# PCB2.net
KiCad netlist of a schematic drawn in EAGLE
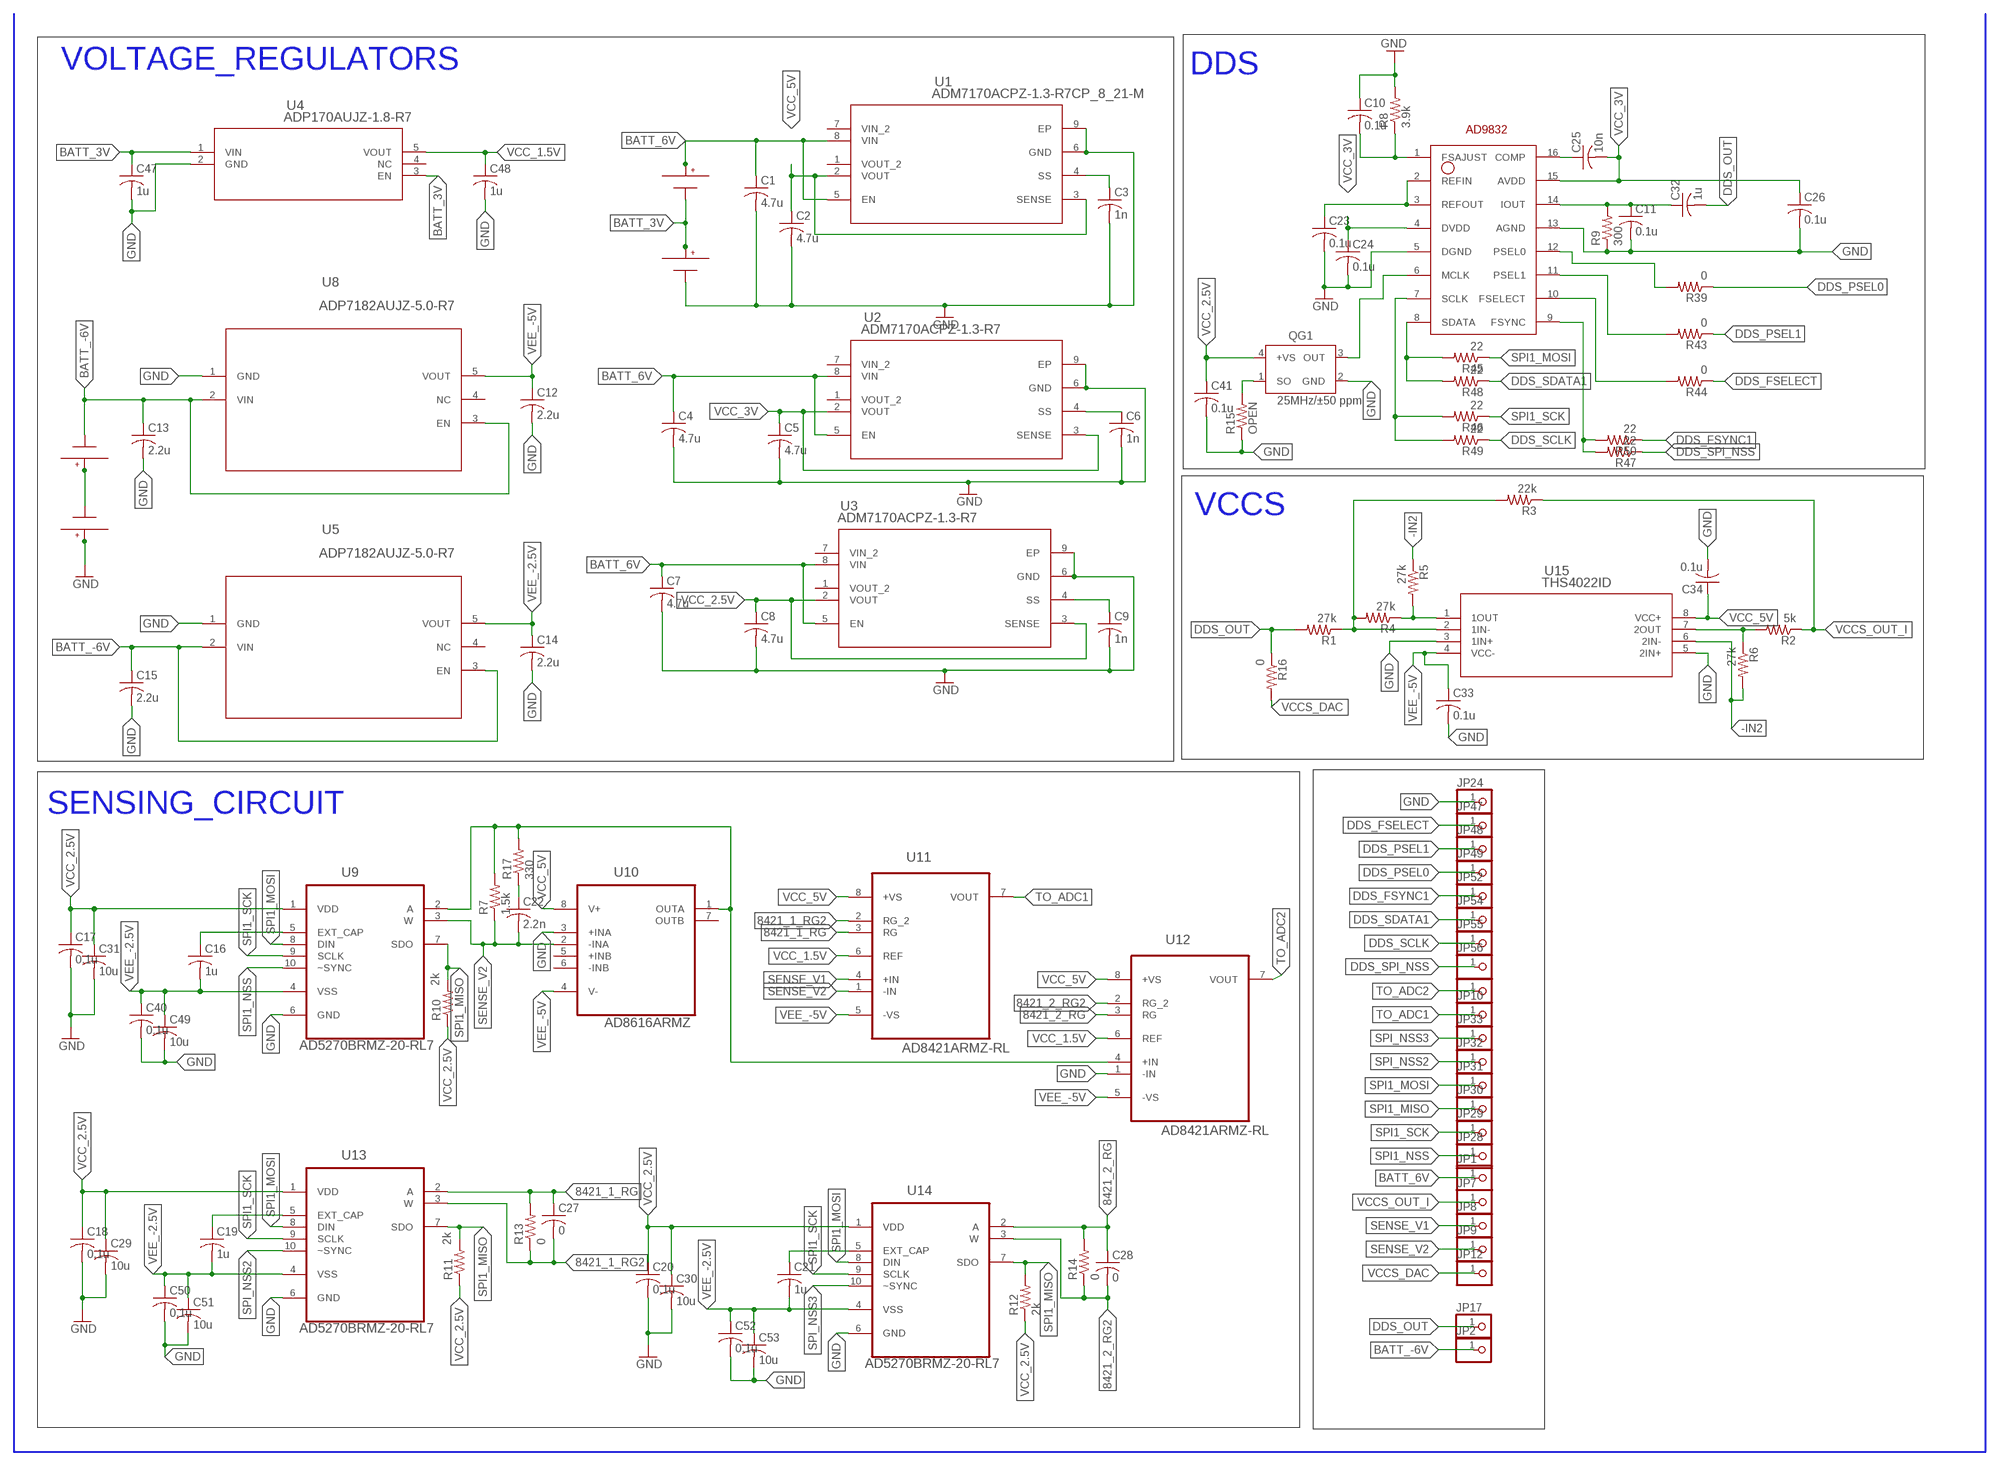
[diagram p0: schematic, sheet 1]

(export (version "E")
  (design (tool "Eeschema 10.0.6"))
  (components
    (comp (ref "C1")
      (value "4.7u")
      (footprint "eagle-import:C0603")
      (libsource (lib "eagle-import") (part "C-USC0603"))
    )
    (comp (ref "C2")
      (value "4.7u")
      (footprint "eagle-import:C0603")
      (libsource (lib "eagle-import") (part "C-USC0603"))
    )
    (comp (ref "C3")
      (value "1n")
      (footprint "eagle-import:C0603")
      (libsource (lib "eagle-import") (part "C-USC0603"))
    )
    (comp (ref "C4")
      (value "4.7u")
      (footprint "eagle-import:C0603")
      (libsource (lib "eagle-import") (part "C-USC0603"))
    )
    (comp (ref "C5")
      (value "4.7u")
      (footprint "eagle-import:C0603")
      (libsource (lib "eagle-import") (part "C-USC0603"))
    )
    (comp (ref "C6")
      (value "1n")
      (footprint "eagle-import:C0603")
      (libsource (lib "eagle-import") (part "C-USC0603"))
    )
    (comp (ref "C7")
      (value "4.7u")
      (footprint "eagle-import:C0603")
      (libsource (lib "eagle-import") (part "C-USC0603"))
    )
    (comp (ref "C8")
      (value "4.7u")
      (footprint "eagle-import:C0603")
      (libsource (lib "eagle-import") (part "C-USC0603"))
    )
    (comp (ref "C9")
      (value "1n")
      (footprint "eagle-import:C0603")
      (libsource (lib "eagle-import") (part "C-USC0603"))
    )
    (comp (ref "C10")
      (value "0.1u")
      (footprint "eagle-import:C0603")
      (libsource (lib "eagle-import") (part "C-USC0603"))
    )
    (comp (ref "C11")
      (value "0.1u")
      (footprint "eagle-import:C0603")
      (libsource (lib "eagle-import") (part "C-USC0603"))
    )
    (comp (ref "C12")
      (value "2.2u")
      (footprint "eagle-import:C0603")
      (libsource (lib "eagle-import") (part "C-USC0603"))
    )
    (comp (ref "C13")
      (value "2.2u")
      (footprint "eagle-import:C0603")
      (libsource (lib "eagle-import") (part "C-USC0603"))
    )
    (comp (ref "C14")
      (value "2.2u")
      (footprint "eagle-import:C0603")
      (libsource (lib "eagle-import") (part "C-USC0603"))
    )
    (comp (ref "C15")
      (value "2.2u")
      (footprint "eagle-import:C0603")
      (libsource (lib "eagle-import") (part "C-USC0603"))
    )
    (comp (ref "C16")
      (value "1u")
      (footprint "eagle-import:C0603")
      (libsource (lib "eagle-import") (part "C-USC0603"))
    )
    (comp (ref "C17")
      (value "0.1u")
      (footprint "eagle-import:C0603")
      (libsource (lib "eagle-import") (part "C-USC0603"))
    )
    (comp (ref "C18")
      (value "0.1u")
      (footprint "eagle-import:C0603")
      (libsource (lib "eagle-import") (part "C-USC0603"))
    )
    (comp (ref "C19")
      (value "1u")
      (footprint "eagle-import:C0603")
      (libsource (lib "eagle-import") (part "C-USC0603"))
    )
    (comp (ref "C20")
      (value "0.1u")
      (footprint "eagle-import:C0603")
      (libsource (lib "eagle-import") (part "C-USC0603"))
    )
    (comp (ref "C21")
      (value "1u")
      (footprint "eagle-import:C0603")
      (libsource (lib "eagle-import") (part "C-USC0603"))
    )
    (comp (ref "C22")
      (value "2.2n")
      (footprint "eagle-import:C0603")
      (libsource (lib "eagle-import") (part "C-USC0603"))
    )
    (comp (ref "C23")
      (value "0.1u")
      (footprint "eagle-import:C0603")
      (libsource (lib "eagle-import") (part "C-USC0603"))
    )
    (comp (ref "C24")
      (value "0.1u")
      (footprint "eagle-import:C0603")
      (libsource (lib "eagle-import") (part "C-USC0603"))
    )
    (comp (ref "C25")
      (value "10n")
      (footprint "eagle-import:C0603")
      (libsource (lib "eagle-import") (part "C-USC0603"))
    )
    (comp (ref "C26")
      (value "0.1u")
      (footprint "eagle-import:C0603")
      (libsource (lib "eagle-import") (part "C-USC0603"))
    )
    (comp (ref "C27")
      (value "0")
      (footprint "eagle-import:C0603")
      (libsource (lib "eagle-import") (part "C-USC0603"))
    )
    (comp (ref "C28")
      (value "0")
      (footprint "eagle-import:C0603")
      (libsource (lib "eagle-import") (part "C-USC0603"))
    )
    (comp (ref "C29")
      (value "10u")
      (footprint "eagle-import:C0603")
      (libsource (lib "eagle-import") (part "C-USC0603"))
    )
    (comp (ref "C30")
      (value "10u")
      (footprint "eagle-import:C0603")
      (libsource (lib "eagle-import") (part "C-USC0603"))
    )
    (comp (ref "C31")
      (value "10u")
      (footprint "eagle-import:C0603")
      (libsource (lib "eagle-import") (part "C-USC0603"))
    )
    (comp (ref "C32")
      (value "1u")
      (footprint "eagle-import:C0603")
      (libsource (lib "eagle-import") (part "C-USC0603"))
    )
    (comp (ref "C33")
      (value "0.1u")
      (footprint "eagle-import:C0603")
      (libsource (lib "eagle-import") (part "C-USC0603"))
    )
    (comp (ref "C34")
      (value "0.1u")
      (footprint "eagle-import:C0603")
      (libsource (lib "eagle-import") (part "C-USC0603"))
    )
    (comp (ref "C40")
      (value "0.1u")
      (footprint "eagle-import:C0603")
      (libsource (lib "eagle-import") (part "C-USC0603"))
    )
    (comp (ref "C41")
      (value "0.1u")
      (footprint "eagle-import:C0603")
      (libsource (lib "eagle-import") (part "C-USC0603"))
    )
    (comp (ref "C47")
      (value "1u")
      (footprint "eagle-import:C0603")
      (libsource (lib "eagle-import") (part "C-USC0603"))
    )
    (comp (ref "C48")
      (value "1u")
      (footprint "eagle-import:C0603")
      (libsource (lib "eagle-import") (part "C-USC0603"))
    )
    (comp (ref "C49")
      (value "10u")
      (footprint "eagle-import:C0603")
      (libsource (lib "eagle-import") (part "C-USC0603"))
    )
    (comp (ref "C50")
      (value "0.1u")
      (footprint "eagle-import:C0603")
      (libsource (lib "eagle-import") (part "C-USC0603"))
    )
    (comp (ref "C51")
      (value "10u")
      (footprint "eagle-import:C0603")
      (libsource (lib "eagle-import") (part "C-USC0603"))
    )
    (comp (ref "C52")
      (value "0.1u")
      (footprint "eagle-import:C0603")
      (libsource (lib "eagle-import") (part "C-USC0603"))
    )
    (comp (ref "C53")
      (value "10u")
      (footprint "eagle-import:C0603")
      (libsource (lib "eagle-import") (part "C-USC0603"))
    )
    (comp (ref "JP1")
      (value "PINHD-1X1")
      (footprint "eagle-import:1X01")
      (libsource (lib "eagle-import") (part "PINHD-1X1"))
    )
    (comp (ref "JP2")
      (value "PINHD-1X1")
      (footprint "eagle-import:1X01")
      (fields (field (name "SPICEPREFIX") "X"))
      (libsource (lib "eagle-import") (part "PINHD-1X1"))
    )
    (comp (ref "JP7")
      (value "PINHD-1X1")
      (footprint "eagle-import:1X01")
      (libsource (lib "eagle-import") (part "PINHD-1X1"))
    )
    (comp (ref "JP8")
      (value "PINHD-1X1")
      (footprint "eagle-import:1X01")
      (libsource (lib "eagle-import") (part "PINHD-1X1"))
    )
    (comp (ref "JP9")
      (value "PINHD-1X1")
      (footprint "eagle-import:1X01")
      (libsource (lib "eagle-import") (part "PINHD-1X1"))
    )
    (comp (ref "JP10")
      (value "PINHD-1X1")
      (footprint "eagle-import:1X01")
      (libsource (lib "eagle-import") (part "PINHD-1X1"))
    )
    (comp (ref "JP11")
      (value "PINHD-1X1")
      (footprint "eagle-import:1X01")
      (libsource (lib "eagle-import") (part "PINHD-1X1"))
    )
    (comp (ref "JP12")
      (value "PINHD-1X1")
      (footprint "eagle-import:1X01")
      (libsource (lib "eagle-import") (part "PINHD-1X1"))
    )
    (comp (ref "JP17")
      (value "PINHD-1X1")
      (footprint "eagle-import:1X01")
      (fields (field (name "SPICEPREFIX") "X"))
      (libsource (lib "eagle-import") (part "PINHD-1X1"))
    )
    (comp (ref "JP24")
      (value "PINHD-1X1")
      (footprint "eagle-import:1X01")
      (libsource (lib "eagle-import") (part "PINHD-1X1"))
    )
    (comp (ref "JP28")
      (value "PINHD-1X1")
      (footprint "eagle-import:1X01")
      (libsource (lib "eagle-import") (part "PINHD-1X1"))
    )
    (comp (ref "JP29")
      (value "PINHD-1X1")
      (footprint "eagle-import:1X01")
      (libsource (lib "eagle-import") (part "PINHD-1X1"))
    )
    (comp (ref "JP30")
      (value "PINHD-1X1")
      (footprint "eagle-import:1X01")
      (libsource (lib "eagle-import") (part "PINHD-1X1"))
    )
    (comp (ref "JP31")
      (value "PINHD-1X1")
      (footprint "eagle-import:1X01")
      (libsource (lib "eagle-import") (part "PINHD-1X1"))
    )
    (comp (ref "JP32")
      (value "PINHD-1X1")
      (footprint "eagle-import:1X01")
      (libsource (lib "eagle-import") (part "PINHD-1X1"))
    )
    (comp (ref "JP33")
      (value "PINHD-1X1")
      (footprint "eagle-import:1X01")
      (libsource (lib "eagle-import") (part "PINHD-1X1"))
    )
    (comp (ref "JP47")
      (value "PINHD-1X1")
      (footprint "eagle-import:1X01")
      (libsource (lib "eagle-import") (part "PINHD-1X1"))
    )
    (comp (ref "JP48")
      (value "PINHD-1X1")
      (footprint "eagle-import:1X01")
      (libsource (lib "eagle-import") (part "PINHD-1X1"))
    )
    (comp (ref "JP49")
      (value "PINHD-1X1")
      (footprint "eagle-import:1X01")
      (libsource (lib "eagle-import") (part "PINHD-1X1"))
    )
    (comp (ref "JP52")
      (value "PINHD-1X1")
      (footprint "eagle-import:1X01")
      (libsource (lib "eagle-import") (part "PINHD-1X1"))
    )
    (comp (ref "JP54")
      (value "PINHD-1X1")
      (footprint "eagle-import:1X01")
      (libsource (lib "eagle-import") (part "PINHD-1X1"))
    )
    (comp (ref "JP55")
      (value "PINHD-1X1")
      (footprint "eagle-import:1X01")
      (libsource (lib "eagle-import") (part "PINHD-1X1"))
    )
    (comp (ref "JP56")
      (value "PINHD-1X1")
      (footprint "eagle-import:1X01")
      (libsource (lib "eagle-import") (part "PINHD-1X1"))
    )
    (comp (ref "QG1")
      (value "25MHz/±50 ppm")
      (footprint "eagle-import:WE-SPXO_IQXO-542")
      (libsource (lib "eagle-import") (part "WE-SPXO_IQXO-542_831056218"))
    )
    (comp (ref "R1")
      (value "27k")
      (footprint "eagle-import:R0603")
      (libsource (lib "eagle-import") (part "R-US_R0603"))
    )
    (comp (ref "R2")
      (value "5k")
      (footprint "eagle-import:R0603")
      (libsource (lib "eagle-import") (part "R-US_R0603"))
    )
    (comp (ref "R3")
      (value "22k")
      (footprint "eagle-import:R0603")
      (libsource (lib "eagle-import") (part "R-US_R0603"))
    )
    (comp (ref "R4")
      (value "27k")
      (footprint "eagle-import:R0603")
      (libsource (lib "eagle-import") (part "R-US_R0603"))
    )
    (comp (ref "R5")
      (value "27k")
      (footprint "eagle-import:R0603")
      (libsource (lib "eagle-import") (part "R-US_R0603"))
    )
    (comp (ref "R6")
      (value "27k")
      (footprint "eagle-import:R0603")
      (libsource (lib "eagle-import") (part "R-US_R0603"))
    )
    (comp (ref "R7")
      (value "1.5k")
      (footprint "eagle-import:R0603")
      (libsource (lib "eagle-import") (part "R-US_R0603"))
    )
    (comp (ref "R8")
      (value "3.9k")
      (footprint "eagle-import:R0603")
      (libsource (lib "eagle-import") (part "R-US_R0603"))
    )
    (comp (ref "R9")
      (value "300")
      (footprint "eagle-import:R0603")
      (libsource (lib "eagle-import") (part "R-US_R0603"))
    )
    (comp (ref "R10")
      (value "2k")
      (footprint "eagle-import:R0603")
      (libsource (lib "eagle-import") (part "R-US_R0603"))
    )
    (comp (ref "R11")
      (value "2k")
      (footprint "eagle-import:R0603")
      (libsource (lib "eagle-import") (part "R-US_R0603"))
    )
    (comp (ref "R12")
      (value "2k")
      (footprint "eagle-import:R0603")
      (libsource (lib "eagle-import") (part "R-US_R0603"))
    )
    (comp (ref "R13")
      (value "0")
      (footprint "eagle-import:R0603")
      (libsource (lib "eagle-import") (part "R-US_R0603"))
    )
    (comp (ref "R14")
      (value "0")
      (footprint "eagle-import:R0603")
      (libsource (lib "eagle-import") (part "R-US_R0603"))
    )
    (comp (ref "R15")
      (value "OPEN")
      (footprint "eagle-import:R0603")
      (libsource (lib "eagle-import") (part "R-US_R0603"))
    )
    (comp (ref "R16")
      (value "0")
      (footprint "eagle-import:R0603")
      (libsource (lib "eagle-import") (part "R-US_R0603"))
    )
    (comp (ref "R17")
      (value "330")
      (footprint "eagle-import:R0603")
      (libsource (lib "eagle-import") (part "R-US_R0603"))
    )
    (comp (ref "R39")
      (value "0")
      (footprint "eagle-import:R0603")
      (libsource (lib "eagle-import") (part "R-US_R0603"))
    )
    (comp (ref "R43")
      (value "0")
      (footprint "eagle-import:R0603")
      (libsource (lib "eagle-import") (part "R-US_R0603"))
    )
    (comp (ref "R44")
      (value "0")
      (footprint "eagle-import:R0603")
      (libsource (lib "eagle-import") (part "R-US_R0603"))
    )
    (comp (ref "R45")
      (value "22")
      (footprint "eagle-import:R0603")
      (libsource (lib "eagle-import") (part "R-US_R0603"))
    )
    (comp (ref "R46")
      (value "22")
      (footprint "eagle-import:R0603")
      (libsource (lib "eagle-import") (part "R-US_R0603"))
    )
    (comp (ref "R47")
      (value "22")
      (footprint "eagle-import:R0603")
      (libsource (lib "eagle-import") (part "R-US_R0603"))
    )
    (comp (ref "R48")
      (value "22")
      (footprint "eagle-import:R0603")
      (libsource (lib "eagle-import") (part "R-US_R0603"))
    )
    (comp (ref "R49")
      (value "22")
      (footprint "eagle-import:R0603")
      (libsource (lib "eagle-import") (part "R-US_R0603"))
    )
    (comp (ref "R50")
      (value "22")
      (footprint "eagle-import:R0603")
      (libsource (lib "eagle-import") (part "R-US_R0603"))
    )
    (comp (ref "U$1")
      (value "AD9832")
      (footprint "eagle-import:TSSOP16")
      (fields (field (name "MF") "Analog Devices"))
      (libsource (lib "eagle-import") (part "AD9832"))
    )
    (comp (ref "U$2")
      (value "BAT-HLD-001")
      (footprint "eagle-import:BAT-HLD-001")
      (fields (field (name "MF") "Linx Technologies"))
      (libsource (lib "eagle-import") (part "BAT-HLD-001"))
    )
    (comp (ref "U$3")
      (value "BAT-HLD-001")
      (footprint "eagle-import:BAT-HLD-001")
      (fields (field (name "MF") "Linx Technologies"))
      (libsource (lib "eagle-import") (part "BAT-HLD-001"))
    )
    (comp (ref "U$4")
      (value "BAT-HLD-001")
      (footprint "eagle-import:BAT-HLD-001")
      (fields (field (name "MF") "Linx Technologies"))
      (libsource (lib "eagle-import") (part "BAT-HLD-001"))
    )
    (comp (ref "U$5")
      (value "BAT-HLD-001")
      (footprint "eagle-import:BAT-HLD-001")
      (fields (field (name "MF") "Linx Technologies"))
      (libsource (lib "eagle-import") (part "BAT-HLD-001"))
    )
    (comp (ref "U1")
      (value "ADM7170ACPZ-1.3-R7CP_8_21-M")
      (footprint "eagle-import:CP_8_21-M")
      (fields (field (name "MANUFACTURER_PART_NUMBER") "ADM7170ACPZ1.3R7"))
      (libsource (lib "eagle-import") (part "ADM7170ACPZ-1.3-R7CP_8_21-M"))
    )
    (comp (ref "U2")
      (value "ADM7170ACPZ-1.3-R7")
      (footprint "eagle-import:CP_8_21")
      (fields (field (name "MANUFACTURER_PART_NUMBER") "ADM7170ACPZ1.3R7"))
      (libsource (lib "eagle-import") (part "ADM7170ACPZ-1.3-R7"))
    )
    (comp (ref "U3")
      (value "ADM7170ACPZ-1.3-R7")
      (footprint "eagle-import:CP_8_21")
      (fields (field (name "MANUFACTURER_PART_NUMBER") "ADM7170ACPZ1.3R7"))
      (libsource (lib "eagle-import") (part "ADM7170ACPZ-1.3-R7"))
    )
    (comp (ref "U4")
      (value "ADP170AUJZ-1.8-R7")
      (footprint "eagle-import:UJ_5")
      (fields (field (name "MANUFACTURER_PART_NUMBER") "ADP170AUJZ1.8R7"))
      (libsource (lib "eagle-import") (part "ADP170AUJZ-1.8-R7"))
    )
    (comp (ref "U5")
      (value "ADP7182AUJZ-5.0-R7")
      (footprint "eagle-import:UJ_5")
      (fields (field (name "MANUFACTURER_PART_NUMBER") "ADP7182AUJZ5.0R7"))
      (libsource (lib "eagle-import") (part "ADP7182AUJZ-5.0-R7"))
    )
    (comp (ref "U8")
      (value "ADP7182AUJZ-5.0-R7")
      (footprint "eagle-import:UJ_5")
      (fields (field (name "MANUFACTURER_PART_NUMBER") "ADP7182AUJZ5.0R7"))
      (libsource (lib "eagle-import") (part "ADP7182AUJZ-5.0-R7"))
    )
    (comp (ref "U9")
      (value "AD5270BRMZ-20-RL7")
      (footprint "eagle-import:SOP50P490X110-10N")
      (fields (field (name "MF") "Analog Devices"))
      (libsource (lib "eagle-import") (part "AD5270BRMZ-20-RL7"))
    )
    (comp (ref "U10")
      (value "AD8616ARMZ")
      (footprint "eagle-import:SOP65P490X110-8N")
      (fields (field (name "MF") "Analog Devices") (field (name "MP") "AD8616ARMZ-REEL"))
      (libsource (lib "eagle-import") (part "AD8616ARMZ"))
    )
    (comp (ref "U11")
      (value "AD8421ARMZ-RL")
      (footprint "eagle-import:SOP65P490X110-8N")
      (fields (field (name "MF") "Analog Devices"))
      (libsource (lib "eagle-import") (part "AD8421ARMZ-RL"))
    )
    (comp (ref "U12")
      (value "AD8421ARMZ-RL")
      (footprint "eagle-import:SOP65P490X110-8N")
      (fields (field (name "MF") "Analog Devices"))
      (libsource (lib "eagle-import") (part "AD8421ARMZ-RL"))
    )
    (comp (ref "U13")
      (value "AD5270BRMZ-20-RL7")
      (footprint "eagle-import:SOP50P490X110-10N")
      (fields (field (name "MF") "Analog Devices"))
      (libsource (lib "eagle-import") (part "AD5270BRMZ-20-RL7"))
    )
    (comp (ref "U14")
      (value "AD5270BRMZ-20-RL7")
      (footprint "eagle-import:SOP50P490X110-10N")
      (fields (field (name "MF") "Analog Devices"))
      (libsource (lib "eagle-import") (part "AD5270BRMZ-20-RL7"))
    )
    (comp (ref "U15")
      (value "THS4022ID")
      (footprint "eagle-import:D8")
      (libsource (lib "eagle-import") (part "THS4022ID"))
    )
  )
  (nets
    (net (code "1") (name "-IN2") (class "Default")
      (node (ref "R5") (pin "1") (pinfunction "1_1") (pintype "passive"))
      (node (ref "R6") (pin "2") (pinfunction "2_2") (pintype "passive"))
      (node (ref "U15") (pin "6") (pinfunction "2IN-_6") (pintype "input"))
    )
    (net (code "2") (name "8421_1_RG") (class "Default")
      (node (ref "C27") (pin "1") (pinfunction "1_1") (pintype "passive"))
      (node (ref "R13") (pin "2") (pinfunction "2_2") (pintype "passive"))
      (node (ref "U11") (pin "3") (pinfunction "RG_3") (pintype "passive"))
      (node (ref "U13") (pin "2") (pinfunction "A_2") (pintype "passive"))
    )
    (net (code "3") (name "8421_1_RG2") (class "Default")
      (node (ref "C27") (pin "2") (pinfunction "2_2") (pintype "passive"))
      (node (ref "R13") (pin "1") (pinfunction "1_1") (pintype "passive"))
      (node (ref "U11") (pin "2") (pinfunction "RG_2_2") (pintype "passive"))
      (node (ref "U13") (pin "3") (pinfunction "W_3") (pintype "passive"))
    )
    (net (code "4") (name "8421_2_RG") (class "Default")
      (node (ref "C28") (pin "1") (pinfunction "1_1") (pintype "passive"))
      (node (ref "R14") (pin "2") (pinfunction "2_2") (pintype "passive"))
      (node (ref "U12") (pin "3") (pinfunction "RG_3") (pintype "passive"))
      (node (ref "U14") (pin "2") (pinfunction "A_2") (pintype "passive"))
    )
    (net (code "5") (name "8421_2_RG2") (class "Default")
      (node (ref "C28") (pin "2") (pinfunction "2_2") (pintype "passive"))
      (node (ref "R14") (pin "1") (pinfunction "1_1") (pintype "passive"))
      (node (ref "U12") (pin "2") (pinfunction "RG_2_2") (pintype "passive"))
      (node (ref "U14") (pin "3") (pinfunction "W_3") (pintype "passive"))
    )
    (net (code "6") (name "BATT_-6V") (class "Default")
      (node (ref "C13") (pin "1") (pinfunction "1_1") (pintype "passive"))
      (node (ref "C15") (pin "1") (pinfunction "1_1") (pintype "passive"))
      (node (ref "JP2") (pin "1") (pinfunction "1_1") (pintype "passive"))
      (node (ref "U$4") (pin "-") (pinfunction "-_-") (pintype "bidirectional"))
      (node (ref "U5") (pin "2") (pinfunction "VIN_2") (pintype "passive"))
      (node (ref "U5") (pin "3") (pinfunction "EN_3") (pintype "passive"))
      (node (ref "U8") (pin "2") (pinfunction "VIN_2") (pintype "passive"))
      (node (ref "U8") (pin "3") (pinfunction "EN_3") (pintype "passive"))
    )
    (net (code "7") (name "BATT_3V") (class "Default")
      (node (ref "C47") (pin "1") (pinfunction "1_1") (pintype "passive"))
      (node (ref "U$2") (pin "-") (pinfunction "-_-") (pintype "bidirectional"))
      (node (ref "U$3") (pin "+@1") (pinfunction "+_+@1") (pintype "bidirectional"))
      (node (ref "U$3") (pin "+@2") (pinfunction "+_+@2") (pintype "bidirectional"))
      (node (ref "U4") (pin "1") (pinfunction "VIN_1") (pintype "input"))
      (node (ref "U4") (pin "3") (pinfunction "EN_3") (pintype "input"))
    )
    (net (code "8") (name "BATT_6V") (class "Default")
      (node (ref "C1") (pin "1") (pinfunction "1_1") (pintype "passive"))
      (node (ref "C4") (pin "1") (pinfunction "1_1") (pintype "passive"))
      (node (ref "C7") (pin "1") (pinfunction "1_1") (pintype "passive"))
      (node (ref "JP1") (pin "1") (pinfunction "1_1") (pintype "passive"))
      (node (ref "U$2") (pin "+@1") (pinfunction "+_+@1") (pintype "bidirectional"))
      (node (ref "U$2") (pin "+@2") (pinfunction "+_+@2") (pintype "bidirectional"))
      (node (ref "U1") (pin "5") (pinfunction "EN_5") (pintype "passive"))
      (node (ref "U1") (pin "8") (pinfunction "VIN_8") (pintype "passive"))
      (node (ref "U2") (pin "5") (pinfunction "EN_5") (pintype "passive"))
      (node (ref "U2") (pin "8") (pinfunction "VIN_8") (pintype "passive"))
      (node (ref "U3") (pin "5") (pinfunction "EN_5") (pintype "passive"))
      (node (ref "U3") (pin "8") (pinfunction "VIN_8") (pintype "passive"))
    )
    (net (code "9") (name "DDS_FSELECT") (class "Default")
      (node (ref "JP47") (pin "1") (pinfunction "1_1") (pintype "passive"))
      (node (ref "R44") (pin "1") (pinfunction "1_1") (pintype "passive"))
    )
    (net (code "10") (name "DDS_FSYNC1") (class "Default")
      (node (ref "JP52") (pin "1") (pinfunction "1_1") (pintype "passive"))
      (node (ref "R50") (pin "1") (pinfunction "1_1") (pintype "passive"))
    )
    (net (code "11") (name "DDS_OUT") (class "Default")
      (node (ref "C32") (pin "2") (pinfunction "2_2") (pintype "passive"))
      (node (ref "JP17") (pin "1") (pinfunction "1_1") (pintype "passive"))
      (node (ref "R1") (pin "2") (pinfunction "2_2") (pintype "passive"))
      (node (ref "R16") (pin "1") (pinfunction "1_1") (pintype "passive"))
    )
    (net (code "12") (name "DDS_PSEL0") (class "Default")
      (node (ref "JP49") (pin "1") (pinfunction "1_1") (pintype "passive"))
      (node (ref "R39") (pin "1") (pinfunction "1_1") (pintype "passive"))
    )
    (net (code "13") (name "DDS_PSEL1") (class "Default")
      (node (ref "JP48") (pin "1") (pinfunction "1_1") (pintype "passive"))
      (node (ref "R43") (pin "1") (pinfunction "1_1") (pintype "passive"))
    )
    (net (code "14") (name "DDS_SCLK") (class "Default")
      (node (ref "JP55") (pin "1") (pinfunction "1_1") (pintype "passive"))
      (node (ref "R49") (pin "1") (pinfunction "1_1") (pintype "passive"))
    )
    (net (code "15") (name "DDS_SDATA1") (class "Default")
      (node (ref "JP54") (pin "1") (pinfunction "1_1") (pintype "passive"))
      (node (ref "R48") (pin "1") (pinfunction "1_1") (pintype "passive"))
    )
    (net (code "16") (name "DDS_SPI_NSS") (class "Default")
      (node (ref "JP56") (pin "1") (pinfunction "1_1") (pintype "passive"))
      (node (ref "R47") (pin "1") (pinfunction "1_1") (pintype "passive"))
    )
    (net (code "17") (name "GND") (class "Default")
      (node (ref "C1") (pin "2") (pinfunction "2_2") (pintype "passive"))
      (node (ref "C10") (pin "1") (pinfunction "1_1") (pintype "passive"))
      (node (ref "C11") (pin "2") (pinfunction "2_2") (pintype "passive"))
      (node (ref "C12") (pin "2") (pinfunction "2_2") (pintype "passive"))
      (node (ref "C13") (pin "2") (pinfunction "2_2") (pintype "passive"))
      (node (ref "C14") (pin "2") (pinfunction "2_2") (pintype "passive"))
      (node (ref "C15") (pin "2") (pinfunction "2_2") (pintype "passive"))
      (node (ref "C17") (pin "2") (pinfunction "2_2") (pintype "passive"))
      (node (ref "C18") (pin "2") (pinfunction "2_2") (pintype "passive"))
      (node (ref "C2") (pin "2") (pinfunction "2_2") (pintype "passive"))
      (node (ref "C20") (pin "2") (pinfunction "2_2") (pintype "passive"))
      (node (ref "C23") (pin "2") (pinfunction "2_2") (pintype "passive"))
      (node (ref "C24") (pin "2") (pinfunction "2_2") (pintype "passive"))
      (node (ref "C26") (pin "2") (pinfunction "2_2") (pintype "passive"))
      (node (ref "C29") (pin "2") (pinfunction "2_2") (pintype "passive"))
      (node (ref "C3") (pin "2") (pinfunction "2_2") (pintype "passive"))
      (node (ref "C30") (pin "2") (pinfunction "2_2") (pintype "passive"))
      (node (ref "C31") (pin "2") (pinfunction "2_2") (pintype "passive"))
      (node (ref "C33") (pin "2") (pinfunction "2_2") (pintype "passive"))
      (node (ref "C34") (pin "2") (pinfunction "2_2") (pintype "passive"))
      (node (ref "C4") (pin "2") (pinfunction "2_2") (pintype "passive"))
      (node (ref "C40") (pin "2") (pinfunction "2_2") (pintype "passive"))
      (node (ref "C41") (pin "2") (pinfunction "2_2") (pintype "passive"))
      (node (ref "C47") (pin "2") (pinfunction "2_2") (pintype "passive"))
      (node (ref "C48") (pin "2") (pinfunction "2_2") (pintype "passive"))
      (node (ref "C49") (pin "2") (pinfunction "2_2") (pintype "passive"))
      (node (ref "C5") (pin "2") (pinfunction "2_2") (pintype "passive"))
      (node (ref "C50") (pin "2") (pinfunction "2_2") (pintype "passive"))
      (node (ref "C51") (pin "2") (pinfunction "2_2") (pintype "passive"))
      (node (ref "C52") (pin "2") (pinfunction "2_2") (pintype "passive"))
      (node (ref "C53") (pin "2") (pinfunction "2_2") (pintype "passive"))
      (node (ref "C6") (pin "2") (pinfunction "2_2") (pintype "passive"))
      (node (ref "C7") (pin "2") (pinfunction "2_2") (pintype "passive"))
      (node (ref "C8") (pin "2") (pinfunction "2_2") (pintype "passive"))
      (node (ref "C9") (pin "2") (pinfunction "2_2") (pintype "passive"))
      (node (ref "JP24") (pin "1") (pinfunction "1_1") (pintype "passive"))
      (node (ref "QG1") (pin "2") (pinfunction "GND_2") (pintype "power_in"))
      (node (ref "R15") (pin "1") (pinfunction "1_1") (pintype "passive"))
      (node (ref "R8") (pin "2") (pinfunction "2_2") (pintype "passive"))
      (node (ref "R9") (pin "1") (pinfunction "1_1") (pintype "passive"))
      (node (ref "U$1") (pin "13") (pinfunction "AGND_13") (pintype "bidirectional"))
      (node (ref "U$1") (pin "5") (pinfunction "DGND_5") (pintype "bidirectional"))
      (node (ref "U$3") (pin "-") (pinfunction "-_-") (pintype "bidirectional"))
      (node (ref "U$5") (pin "+@1") (pinfunction "+_+@1") (pintype "bidirectional"))
      (node (ref "U$5") (pin "+@2") (pinfunction "+_+@2") (pintype "bidirectional"))
      (node (ref "U1") (pin "6") (pinfunction "GND_6") (pintype "passive"))
      (node (ref "U1") (pin "9") (pinfunction "EP_9") (pintype "passive"))
      (node (ref "U10") (pin "3") (pinfunction "+INA_3") (pintype "input"))
      (node (ref "U12") (pin "1") (pinfunction "-IN_1") (pintype "input"))
      (node (ref "U13") (pin "6") (pinfunction "GND_6") (pintype "passive"))
      (node (ref "U14") (pin "6") (pinfunction "GND_6") (pintype "passive"))
      (node (ref "U15") (pin "3") (pinfunction "1IN+_3") (pintype "input"))
      (node (ref "U15") (pin "5") (pinfunction "2IN+_5") (pintype "input"))
      (node (ref "U2") (pin "6") (pinfunction "GND_6") (pintype "passive"))
      (node (ref "U2") (pin "9") (pinfunction "EP_9") (pintype "passive"))
      (node (ref "U3") (pin "6") (pinfunction "GND_6") (pintype "passive"))
      (node (ref "U3") (pin "9") (pinfunction "EP_9") (pintype "passive"))
      (node (ref "U4") (pin "2") (pinfunction "GND_2") (pintype "power_in"))
      (node (ref "U5") (pin "1") (pinfunction "GND_1") (pintype "passive"))
      (node (ref "U8") (pin "1") (pinfunction "GND_1") (pintype "passive"))
      (node (ref "U9") (pin "6") (pinfunction "GND_6") (pintype "passive"))
    )
    (net (code "18") (name "Net-(C22-Pad1)") (class "Default")
      (node (ref "C22") (pin "1") (pinfunction "1_1") (pintype "passive"))
      (node (ref "R17") (pin "1") (pinfunction "1_1") (pintype "passive"))
    )
    (net (code "19") (name "Net-(QG1-OUT)") (class "Default")
      (node (ref "QG1") (pin "3") (pinfunction "OUT_3") (pintype "output"))
      (node (ref "U$1") (pin "6") (pinfunction "MCLK_6") (pintype "bidirectional"))
    )
    (net (code "20") (name "Net-(QG1-SO)") (class "Default")
      (node (ref "QG1") (pin "1") (pinfunction "SO_1") (pintype "input"))
      (node (ref "R15") (pin "2") (pinfunction "2_2") (pintype "passive"))
    )
    (net (code "21") (name "Net-(U$1-COMP)") (class "Default")
      (node (ref "C25") (pin "1") (pinfunction "1_1") (pintype "passive"))
      (node (ref "U$1") (pin "16") (pinfunction "COMP_16") (pintype "bidirectional"))
    )
    (net (code "22") (name "Net-(U$1-FSAJUST)") (class "Default")
      (node (ref "C10") (pin "2") (pinfunction "2_2") (pintype "passive"))
      (node (ref "R8") (pin "1") (pinfunction "1_1") (pintype "passive"))
      (node (ref "U$1") (pin "1") (pinfunction "FSAJUST_1") (pintype "bidirectional"))
    )
    (net (code "23") (name "Net-(U$1-FSELECT)") (class "Default")
      (node (ref "R44") (pin "2") (pinfunction "2_2") (pintype "passive"))
      (node (ref "U$1") (pin "10") (pinfunction "FSELECT_10") (pintype "bidirectional"))
    )
    (net (code "24") (name "Net-(U$1-FSYNC)") (class "Default")
      (node (ref "R47") (pin "2") (pinfunction "2_2") (pintype "passive"))
      (node (ref "R50") (pin "2") (pinfunction "2_2") (pintype "passive"))
      (node (ref "U$1") (pin "9") (pinfunction "FSYNC_9") (pintype "bidirectional"))
    )
    (net (code "25") (name "Net-(U$1-IOUT)") (class "Default")
      (node (ref "C11") (pin "1") (pinfunction "1_1") (pintype "passive"))
      (node (ref "C32") (pin "1") (pinfunction "1_1") (pintype "passive"))
      (node (ref "R9") (pin "2") (pinfunction "2_2") (pintype "passive"))
      (node (ref "U$1") (pin "14") (pinfunction "IOUT_14") (pintype "bidirectional"))
    )
    (net (code "26") (name "Net-(U$1-PSEL0)") (class "Default")
      (node (ref "R39") (pin "2") (pinfunction "2_2") (pintype "passive"))
      (node (ref "U$1") (pin "12") (pinfunction "PSEL0_12") (pintype "bidirectional"))
    )
    (net (code "27") (name "Net-(U$1-PSEL1)") (class "Default")
      (node (ref "R43") (pin "2") (pinfunction "2_2") (pintype "passive"))
      (node (ref "U$1") (pin "11") (pinfunction "PSEL1_11") (pintype "bidirectional"))
    )
    (net (code "28") (name "Net-(U$1-REFIN)") (class "Default")
      (node (ref "C23") (pin "1") (pinfunction "1_1") (pintype "passive"))
      (node (ref "U$1") (pin "2") (pinfunction "REFIN_2") (pintype "bidirectional"))
      (node (ref "U$1") (pin "3") (pinfunction "REFOUT_3") (pintype "bidirectional"))
    )
    (net (code "29") (name "Net-(U$1-SCLK)") (class "Default")
      (node (ref "R46") (pin "2") (pinfunction "2_2") (pintype "passive"))
      (node (ref "R49") (pin "2") (pinfunction "2_2") (pintype "passive"))
      (node (ref "U$1") (pin "7") (pinfunction "SCLK_7") (pintype "bidirectional"))
    )
    (net (code "30") (name "Net-(U$1-SDATA)") (class "Default")
      (node (ref "R45") (pin "2") (pinfunction "2_2") (pintype "passive"))
      (node (ref "R48") (pin "2") (pinfunction "2_2") (pintype "passive"))
      (node (ref "U$1") (pin "8") (pinfunction "SDATA_8") (pintype "bidirectional"))
    )
    (net (code "31") (name "Net-(U$4-+-Pad+@1)") (class "Default")
      (node (ref "U$4") (pin "+@1") (pinfunction "+_+@1") (pintype "bidirectional"))
      (node (ref "U$4") (pin "+@2") (pinfunction "+_+@2") (pintype "bidirectional"))
      (node (ref "U$5") (pin "-") (pinfunction "-_-") (pintype "bidirectional"))
    )
    (net (code "32") (name "Net-(U1-SS)") (class "Default")
      (node (ref "C3") (pin "1") (pinfunction "1_1") (pintype "passive"))
      (node (ref "U1") (pin "4") (pinfunction "SS_4") (pintype "passive"))
    )
    (net (code "33") (name "Net-(U2-SS)") (class "Default")
      (node (ref "C6") (pin "1") (pinfunction "1_1") (pintype "passive"))
      (node (ref "U2") (pin "4") (pinfunction "SS_4") (pintype "passive"))
    )
    (net (code "34") (name "Net-(U3-SS)") (class "Default")
      (node (ref "C9") (pin "1") (pinfunction "1_1") (pintype "passive"))
      (node (ref "U3") (pin "4") (pinfunction "SS_4") (pintype "passive"))
    )
    (net (code "35") (name "Net-(U9-EXT_CAP)") (class "Default")
      (node (ref "C16") (pin "1") (pinfunction "1_1") (pintype "passive"))
      (node (ref "U9") (pin "5") (pinfunction "EXT_CAP_5") (pintype "passive"))
    )
    (net (code "36") (name "Net-(U10-OUTA)") (class "Default")
      (node (ref "R17") (pin "2") (pinfunction "2_2") (pintype "passive"))
      (node (ref "R7") (pin "2") (pinfunction "2_2") (pintype "passive"))
      (node (ref "U10") (pin "1") (pinfunction "OUTA_1") (pintype "output"))
      (node (ref "U12") (pin "4") (pinfunction "+IN_4") (pintype "input"))
      (node (ref "U9") (pin "2") (pinfunction "A_2") (pintype "passive"))
    )
    (net (code "37") (name "Net-(U13-EXT_CAP)") (class "Default")
      (node (ref "C19") (pin "1") (pinfunction "1_1") (pintype "passive"))
      (node (ref "U13") (pin "5") (pinfunction "EXT_CAP_5") (pintype "passive"))
    )
    (net (code "38") (name "Net-(U14-EXT_CAP)") (class "Default")
      (node (ref "C21") (pin "1") (pinfunction "1_1") (pintype "passive"))
      (node (ref "U14") (pin "5") (pinfunction "EXT_CAP_5") (pintype "passive"))
    )
    (net (code "39") (name "Net-(U15-1IN-)") (class "Default")
      (node (ref "R1") (pin "1") (pinfunction "1_1") (pintype "passive"))
      (node (ref "R3") (pin "2") (pinfunction "2_2") (pintype "passive"))
      (node (ref "R4") (pin "2") (pinfunction "2_2") (pintype "passive"))
      (node (ref "U15") (pin "2") (pinfunction "1IN-_2") (pintype "input"))
    )
    (net (code "40") (name "Net-(U15-1OUT)") (class "Default")
      (node (ref "R4") (pin "1") (pinfunction "1_1") (pintype "passive"))
      (node (ref "R5") (pin "2") (pinfunction "2_2") (pintype "passive"))
      (node (ref "U15") (pin "1") (pinfunction "1OUT_1") (pintype "output"))
    )
    (net (code "41") (name "Net-(U15-2OUT)") (class "Default")
      (node (ref "R2") (pin "2") (pinfunction "2_2") (pintype "passive"))
      (node (ref "R6") (pin "1") (pinfunction "1_1") (pintype "passive"))
      (node (ref "U15") (pin "7") (pinfunction "2OUT_7") (pintype "output"))
    )
    (net (code "42") (name "SENSE_V1") (class "Default")
      (node (ref "JP8") (pin "1") (pinfunction "1_1") (pintype "passive"))
      (node (ref "U11") (pin "4") (pinfunction "+IN_4") (pintype "input"))
    )
    (net (code "43") (name "SENSE_V2") (class "Default")
      (node (ref "C22") (pin "2") (pinfunction "2_2") (pintype "passive"))
      (node (ref "JP9") (pin "1") (pinfunction "1_1") (pintype "passive"))
      (node (ref "R7") (pin "1") (pinfunction "1_1") (pintype "passive"))
      (node (ref "U10") (pin "2") (pinfunction "-INA_2") (pintype "input"))
      (node (ref "U11") (pin "1") (pinfunction "-IN_1") (pintype "input"))
      (node (ref "U9") (pin "3") (pinfunction "W_3") (pintype "passive"))
    )
    (net (code "44") (name "SPI1_MISO") (class "Default")
      (node (ref "JP30") (pin "1") (pinfunction "1_1") (pintype "passive"))
      (node (ref "R10") (pin "2") (pinfunction "2_2") (pintype "passive"))
      (node (ref "R11") (pin "2") (pinfunction "2_2") (pintype "passive"))
      (node (ref "R12") (pin "2") (pinfunction "2_2") (pintype "passive"))
      (node (ref "U13") (pin "7") (pinfunction "SDO_7") (pintype "output"))
      (node (ref "U14") (pin "7") (pinfunction "SDO_7") (pintype "output"))
      (node (ref "U9") (pin "7") (pinfunction "SDO_7") (pintype "output"))
    )
    (net (code "45") (name "SPI1_MOSI") (class "Default")
      (node (ref "JP31") (pin "1") (pinfunction "1_1") (pintype "passive"))
      (node (ref "R45") (pin "1") (pinfunction "1_1") (pintype "passive"))
      (node (ref "U13") (pin "8") (pinfunction "DIN_8") (pintype "input"))
      (node (ref "U14") (pin "8") (pinfunction "DIN_8") (pintype "input"))
      (node (ref "U9") (pin "8") (pinfunction "DIN_8") (pintype "input"))
    )
    (net (code "46") (name "SPI1_NSS") (class "Default")
      (node (ref "JP28") (pin "1") (pinfunction "1_1") (pintype "passive"))
      (node (ref "U9") (pin "10") (pinfunction "~{SYNC}_10") (pintype "input"))
    )
    (net (code "47") (name "SPI1_SCK") (class "Default")
      (node (ref "JP29") (pin "1") (pinfunction "1_1") (pintype "passive"))
      (node (ref "R46") (pin "1") (pinfunction "1_1") (pintype "passive"))
      (node (ref "U13") (pin "9") (pinfunction "SCLK_9") (pintype "input"))
      (node (ref "U14") (pin "9") (pinfunction "SCLK_9") (pintype "input"))
      (node (ref "U9") (pin "9") (pinfunction "SCLK_9") (pintype "input"))
    )
    (net (code "48") (name "SPI_NSS2") (class "Default")
      (node (ref "JP32") (pin "1") (pinfunction "1_1") (pintype "passive"))
      (node (ref "U13") (pin "10") (pinfunction "~{SYNC}_10") (pintype "input"))
    )
    (net (code "49") (name "SPI_NSS3") (class "Default")
      (node (ref "JP33") (pin "1") (pinfunction "1_1") (pintype "passive"))
      (node (ref "U14") (pin "10") (pinfunction "~{SYNC}_10") (pintype "input"))
    )
    (net (code "50") (name "TO_ADC1") (class "Default")
      (node (ref "JP10") (pin "1") (pinfunction "1_1") (pintype "passive"))
      (node (ref "U11") (pin "7") (pinfunction "VOUT_7") (pintype "output"))
    )
    (net (code "51") (name "TO_ADC2") (class "Default")
      (node (ref "JP11") (pin "1") (pinfunction "1_1") (pintype "passive"))
      (node (ref "U12") (pin "7") (pinfunction "VOUT_7") (pintype "output"))
    )
    (net (code "52") (name "VCCS_DAC") (class "Default")
      (node (ref "JP12") (pin "1") (pinfunction "1_1") (pintype "passive"))
      (node (ref "R16") (pin "2") (pinfunction "2_2") (pintype "passive"))
    )
    (net (code "53") (name "VCCS_OUT_I") (class "Default")
      (node (ref "JP7") (pin "1") (pinfunction "1_1") (pintype "passive"))
      (node (ref "R2") (pin "1") (pinfunction "1_1") (pintype "passive"))
      (node (ref "R3") (pin "1") (pinfunction "1_1") (pintype "passive"))
    )
    (net (code "54") (name "VCC_1.5V") (class "Default")
      (node (ref "C48") (pin "1") (pinfunction "1_1") (pintype "passive"))
      (node (ref "U11") (pin "6") (pinfunction "REF_6") (pintype "power_in"))
      (node (ref "U12") (pin "6") (pinfunction "REF_6") (pintype "power_in"))
      (node (ref "U4") (pin "5") (pinfunction "VOUT_5") (pintype "output"))
    )
    (net (code "55") (name "VCC_2.5V") (class "Default")
      (node (ref "C17") (pin "1") (pinfunction "1_1") (pintype "passive"))
      (node (ref "C18") (pin "1") (pinfunction "1_1") (pintype "passive"))
      (node (ref "C20") (pin "1") (pinfunction "1_1") (pintype "passive"))
      (node (ref "C29") (pin "1") (pinfunction "1_1") (pintype "passive"))
      (node (ref "C30") (pin "1") (pinfunction "1_1") (pintype "passive"))
      (node (ref "C31") (pin "1") (pinfunction "1_1") (pintype "passive"))
      (node (ref "C41") (pin "1") (pinfunction "1_1") (pintype "passive"))
      (node (ref "C8") (pin "1") (pinfunction "1_1") (pintype "passive"))
      (node (ref "QG1") (pin "4") (pinfunction "+VS_4") (pintype "power_in"))
      (node (ref "R10") (pin "1") (pinfunction "1_1") (pintype "passive"))
      (node (ref "R11") (pin "1") (pinfunction "1_1") (pintype "passive"))
      (node (ref "R12") (pin "1") (pinfunction "1_1") (pintype "passive"))
      (node (ref "U13") (pin "1") (pinfunction "VDD_1") (pintype "power_in"))
      (node (ref "U14") (pin "1") (pinfunction "VDD_1") (pintype "power_in"))
      (node (ref "U3") (pin "2") (pinfunction "VOUT_2") (pintype "passive"))
      (node (ref "U3") (pin "3") (pinfunction "SENSE_3") (pintype "passive"))
      (node (ref "U9") (pin "1") (pinfunction "VDD_1") (pintype "power_in"))
    )
    (net (code "56") (name "VCC_3V") (class "Default")
      (node (ref "C24") (pin "1") (pinfunction "1_1") (pintype "passive"))
      (node (ref "C25") (pin "2") (pinfunction "2_2") (pintype "passive"))
      (node (ref "C26") (pin "1") (pinfunction "1_1") (pintype "passive"))
      (node (ref "C5") (pin "1") (pinfunction "1_1") (pintype "passive"))
      (node (ref "U$1") (pin "15") (pinfunction "AVDD_15") (pintype "bidirectional"))
      (node (ref "U$1") (pin "4") (pinfunction "DVDD_4") (pintype "bidirectional"))
      (node (ref "U2") (pin "2") (pinfunction "VOUT_2") (pintype "passive"))
      (node (ref "U2") (pin "3") (pinfunction "SENSE_3") (pintype "passive"))
    )
    (net (code "57") (name "VCC_5V") (class "Default")
      (node (ref "C2") (pin "1") (pinfunction "1_1") (pintype "passive"))
      (node (ref "C34") (pin "1") (pinfunction "1_1") (pintype "passive"))
      (node (ref "U1") (pin "2") (pinfunction "VOUT_2") (pintype "passive"))
      (node (ref "U1") (pin "3") (pinfunction "SENSE_3") (pintype "passive"))
      (node (ref "U10") (pin "8") (pinfunction "V+_8") (pintype "power_in"))
      (node (ref "U11") (pin "8") (pinfunction "+VS_8") (pintype "power_in"))
      (node (ref "U12") (pin "8") (pinfunction "+VS_8") (pintype "power_in"))
      (node (ref "U15") (pin "8") (pinfunction "VCC+_8") (pintype "power_in"))
    )
    (net (code "58") (name "VEE_-2.5V") (class "Default")
      (node (ref "C14") (pin "1") (pinfunction "1_1") (pintype "passive"))
      (node (ref "C16") (pin "2") (pinfunction "2_2") (pintype "passive"))
      (node (ref "C19") (pin "2") (pinfunction "2_2") (pintype "passive"))
      (node (ref "C21") (pin "2") (pinfunction "2_2") (pintype "passive"))
      (node (ref "C40") (pin "1") (pinfunction "1_1") (pintype "passive"))
      (node (ref "C49") (pin "1") (pinfunction "1_1") (pintype "passive"))
      (node (ref "C50") (pin "1") (pinfunction "1_1") (pintype "passive"))
      (node (ref "C51") (pin "1") (pinfunction "1_1") (pintype "passive"))
      (node (ref "C52") (pin "1") (pinfunction "1_1") (pintype "passive"))
      (node (ref "C53") (pin "1") (pinfunction "1_1") (pintype "passive"))
      (node (ref "U13") (pin "4") (pinfunction "VSS_4") (pintype "power_in"))
      (node (ref "U14") (pin "4") (pinfunction "VSS_4") (pintype "power_in"))
      (node (ref "U5") (pin "5") (pinfunction "VOUT_5") (pintype "output"))
      (node (ref "U9") (pin "4") (pinfunction "VSS_4") (pintype "power_in"))
    )
    (net (code "59") (name "VEE_-5V") (class "Default")
      (node (ref "C12") (pin "1") (pinfunction "1_1") (pintype "passive"))
      (node (ref "C33") (pin "1") (pinfunction "1_1") (pintype "passive"))
      (node (ref "U10") (pin "4") (pinfunction "V-_4") (pintype "power_in"))
      (node (ref "U11") (pin "5") (pinfunction "-VS_5") (pintype "power_in"))
      (node (ref "U12") (pin "5") (pinfunction "-VS_5") (pintype "power_in"))
      (node (ref "U15") (pin "4") (pinfunction "VCC-_4") (pintype "power_in"))
      (node (ref "U8") (pin "5") (pinfunction "VOUT_5") (pintype "output"))
    )
    (net (code "60") (name "unconnected-(U1-VIN_2-Pad7)") (class "Default")
      (node (ref "U1") (pin "7") (pinfunction "VIN_2_7") (pintype "passive"))
    )
    (net (code "61") (name "unconnected-(U1-VOUT_2-Pad1)") (class "Default")
      (node (ref "U1") (pin "1") (pinfunction "VOUT_2_1") (pintype "passive"))
    )
    (net (code "62") (name "unconnected-(U2-VIN_2-Pad7)") (class "Default")
      (node (ref "U2") (pin "7") (pinfunction "VIN_2_7") (pintype "passive"))
    )
    (net (code "63") (name "unconnected-(U2-VOUT_2-Pad1)") (class "Default")
      (node (ref "U2") (pin "1") (pinfunction "VOUT_2_1") (pintype "passive"))
    )
    (net (code "64") (name "unconnected-(U3-VIN_2-Pad7)") (class "Default")
      (node (ref "U3") (pin "7") (pinfunction "VIN_2_7") (pintype "passive"))
    )
    (net (code "65") (name "unconnected-(U3-VOUT_2-Pad1)") (class "Default")
      (node (ref "U3") (pin "1") (pinfunction "VOUT_2_1") (pintype "passive"))
    )
    (net (code "66") (name "unconnected-(U4-NC-Pad4)") (class "Default")
      (node (ref "U4") (pin "4") (pinfunction "NC_4") (pintype "no_connect"))
    )
    (net (code "67") (name "unconnected-(U5-NC-Pad4)") (class "Default")
      (node (ref "U5") (pin "4") (pinfunction "NC_4") (pintype "no_connect"))
    )
    (net (code "68") (name "unconnected-(U8-NC-Pad4)") (class "Default")
      (node (ref "U8") (pin "4") (pinfunction "NC_4") (pintype "no_connect"))
    )
    (net (code "69") (name "unconnected-(U10-+INB-Pad5)") (class "Default")
      (node (ref "U10") (pin "5") (pinfunction "+INB_5") (pintype "input"))
    )
    (net (code "70") (name "unconnected-(U10--INB-Pad6)") (class "Default")
      (node (ref "U10") (pin "6") (pinfunction "-INB_6") (pintype "input"))
    )
    (net (code "71") (name "unconnected-(U10-OUTB-Pad7)") (class "Default")
      (node (ref "U10") (pin "7") (pinfunction "OUTB_7") (pintype "output"))
    )
  )
)
